# 01_Main.net
KiCad netlist of a schematic drawn in Altium Designer
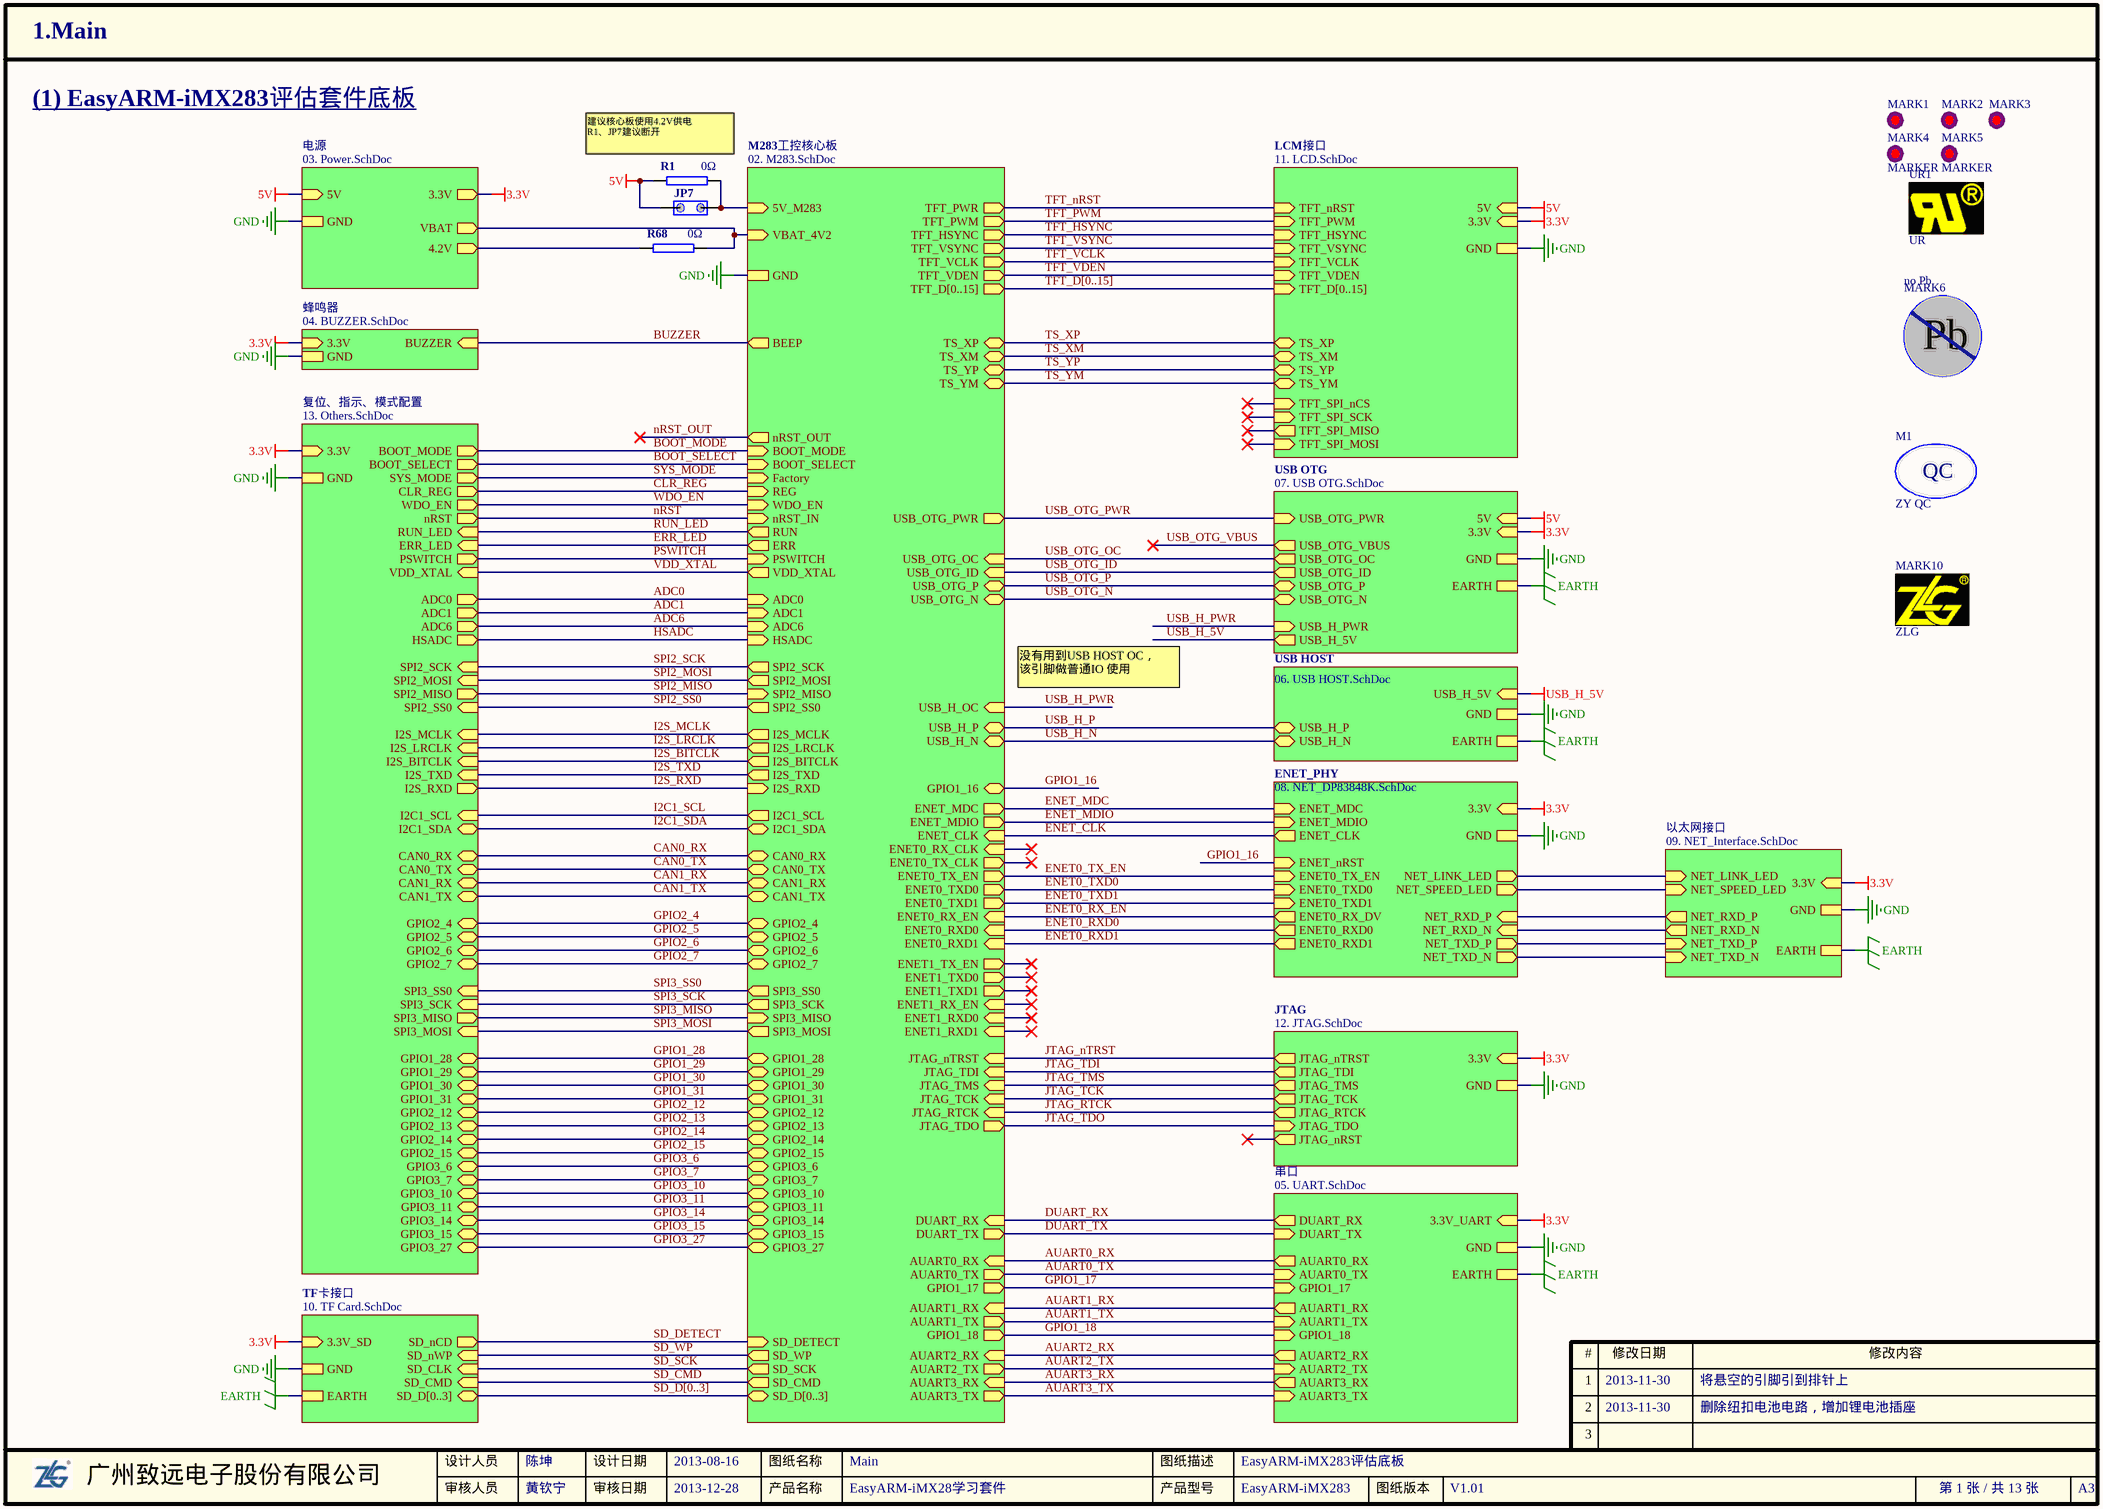
[diagram p0: 01. Main.SchDoc]

(export (version "E")
  (design (tool "Eeschema 10.0.6"))
  (components
    (comp (ref "JP7") (value "120Ω_EN") (footprint "SIP-2") (libsource (lib "无需物料号元件") (part "JMP2")))
    (comp (ref "M1") (value "ZY QC") (footprint "ZY_QC") (libsource (lib "无需物料号元件") (part "ZY QC")))
    (comp (ref "MARK1") (value "MARKER") (footprint "MARKER-C") (libsource (lib "无需物料号元件") (part "MARKER")))
    (comp (ref "MARK2") (value "MARKER") (footprint "MARKER-C") (libsource (lib "无需物料号元件") (part "MARKER")))
    (comp (ref "MARK3") (value "MARKER") (footprint "MARKER-C") (libsource (lib "无需物料号元件") (part "MARKER")))
    (comp (ref "MARK4") (value "MARKER") (footprint "MARKER-C") (libsource (lib "无需物料号元件") (part "MARKER")))
    (comp (ref "MARK5") (value "MARKER") (footprint "MARKER-C") (libsource (lib "无需物料号元件") (part "MARKER")))
    (comp (ref "MARK6") (value "no Pb") (footprint "ZY_no Pb-4") (libsource (lib "无需物料号元件") (part "no Pb")))
    (comp (ref "MARK10") (value "ZLG") (footprint "ZLG0.7") (libsource (lib "无需物料号元件") (part "ZLG")))
    (comp (ref "R1")
      (value "0Ω")
      (footprint "0603R")
      (description "0Ω,0603,*,RoHS")
      (libsource (lib "ErpMaterialData") (part "RES2"))
    )
    (comp (ref "R68")
      (value "0Ω")
      (footprint "0603R")
      (description "0Ω,0603,*,RoHS")
      (libsource (lib "ErpMaterialData") (part "RES2"))
    )
    (comp (ref "UR1") (value "UR") (footprint "ZY_UR-3X2") (libsource (lib "无需物料号元件") (part "UR")))
  )
  (nets
    (net (code "21") (name "/4.2V") (class "Default")
      (node (ref "R68") (pin "1") (pinfunction "1_1") (pintype "passive"))
    )
    (net (code "22") (name "/5V_M283") (class "Default")
      (node (ref "JP7") (pin "2") (pinfunction "2_2") (pintype "passive"))
      (node (ref "R1") (pin "2") (pinfunction "2_2") (pintype "passive"))
    )
    (net (code "145") (name "/VBAT") (class "Default")
      (node (ref "R68") (pin "2") (pinfunction "2_2") (pintype "passive"))
    )
    (net (code "151") (name "5V") (class "Default")
      (node (ref "JP7") (pin "1") (pinfunction "1_1") (pintype "passive"))
      (node (ref "R1") (pin "1") (pinfunction "1_1") (pintype "passive"))
    )
    (net (code "155") (name "unconnected-(MARK1-Pad0)") (class "Default")
      (node (ref "MARK1") (pin "0") (pintype "passive"))
    )
    (net (code "156") (name "unconnected-(MARK2-Pad0)") (class "Default")
      (node (ref "MARK2") (pin "0") (pintype "passive"))
    )
    (net (code "157") (name "unconnected-(MARK3-Pad0)") (class "Default")
      (node (ref "MARK3") (pin "0") (pintype "passive"))
    )
    (net (code "158") (name "unconnected-(MARK4-Pad0)") (class "Default")
      (node (ref "MARK4") (pin "0") (pintype "passive"))
    )
    (net (code "159") (name "unconnected-(MARK5-Pad0)") (class "Default")
      (node (ref "MARK5") (pin "0") (pintype "passive"))
    )
  )
)
